# Dart_Controller_SCH2.net
KiCad netlist of a schematic drawn in Altium Designer
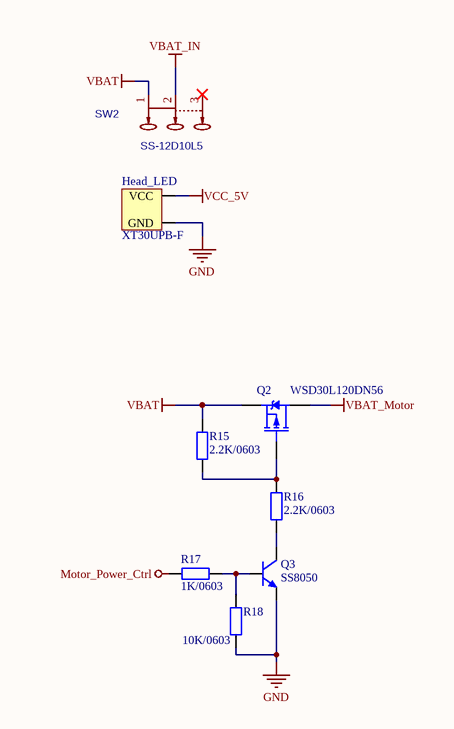
[diagram p0: Dart_Controller_SCH2.SchDoc]

(export (version "E")
  (design (tool "Eeschema 10.0.6"))
  (components
    (comp (ref "Head_LED")
      (value "XT30UPB-F")
      (footprint "XT30PW-F")
      (description "母头（卧式）")
      (libsource (lib "Dart_Controller_Schlib") (part "XT30-PW-F"))
    )
    (comp (ref "Q2")
      (value "WSD30L120DN56")
      (footprint "POWERVDFN-8_L6.0-W5.0-P1.27-BL")
      (description "P沟道场效应管")
      (libsource (lib "Dart_Controller_Schlib") (part "WSD30L120DN56"))
    )
    (comp (ref "Q3")
      (value "SS8050")
      (footprint "SOT23-3L")
      (description "高频放大-NPN型")
      (fields (field (name "版权归属") "封装库来自淘宝 ID：黄晶宝石"))
      (libsource (lib "Dart_Controller_Schlib") (part "SS8050-SMD"))
    )
    (comp (ref "R15")
      (value "2.2K/0603")
      (footprint "R 0603_M")
      (description "贴片电阻")
      (fields (field (name "版权归属") "来自淘宝 ID：黄晶宝石"))
      (libsource (lib "Dart_Controller_Schlib") (part "R 0603"))
    )
    (comp (ref "R16")
      (value "2.2K/0603")
      (footprint "R 0603_M")
      (description "贴片电阻")
      (fields (field (name "版权归属") "来自淘宝 ID：黄晶宝石"))
      (libsource (lib "Dart_Controller_Schlib") (part "R 0603"))
    )
    (comp (ref "R17")
      (value "1K/0603")
      (footprint "R 0603_M")
      (description "贴片电阻")
      (fields (field (name "版权归属") "来自淘宝 ID：黄晶宝石"))
      (libsource (lib "Dart_Controller_Schlib") (part "R 0603"))
    )
    (comp (ref "R18")
      (value "10K/0603")
      (footprint "R 0603_M")
      (description "贴片电阻")
      (fields (field (name "版权归属") "来自淘宝 ID：黄晶宝石"))
      (libsource (lib "Dart_Controller_Schlib") (part "R 0603"))
    )
    (comp (ref "SW2")
      (value "SS-12D10L5")
      (footprint "SW-TH_SS-12D10L5")
      (description "滑动开关")
      (fields (field (name "MANUFACTURER") "XKB Connectivity(中国星坤)") (field (name "CONTRIBUTOR") "LCSC"))
      (libsource (lib "Dart_Controller_Schlib") (part "SS-12D10L5"))
    )
  )
  (nets
    (net (code "1") (name "GND") (class "Default")
      (node (ref "Head_LED") (pin "2") (pinfunction "GND_2") (pintype "passive"))
      (node (ref "Q3") (pin "2") (pinfunction "E_2") (pintype "passive"))
      (node (ref "R18") (pin "2") (pinfunction "2_2") (pintype "passive"))
    )
    (net (code "2") (name "Motor_Power_Ctrl") (class "Default")
      (node (ref "R17") (pin "2") (pinfunction "2_2") (pintype "passive"))
    )
    (net (code "3") (name "Net-(Q2-PadG)") (class "Default")
      (node (ref "Q2") (pin "G") (pinfunction "G_G") (pintype "passive"))
      (node (ref "R15") (pin "1") (pinfunction "1_1") (pintype "passive"))
      (node (ref "R16") (pin "2") (pinfunction "2_2") (pintype "passive"))
    )
    (net (code "4") (name "Net-(Q3-B)") (class "Default")
      (node (ref "Q3") (pin "1") (pinfunction "B_1") (pintype "passive"))
      (node (ref "R17") (pin "1") (pinfunction "1_1") (pintype "passive"))
      (node (ref "R18") (pin "1") (pinfunction "1_1") (pintype "passive"))
    )
    (net (code "5") (name "Net-(Q3-C)") (class "Default")
      (node (ref "Q3") (pin "3") (pinfunction "C_3") (pintype "passive"))
      (node (ref "R16") (pin "1") (pinfunction "1_1") (pintype "passive"))
    )
    (net (code "6") (name "VBAT") (class "Default")
      (node (ref "Q2") (pin "S") (pinfunction "S_S") (pintype "passive"))
      (node (ref "R15") (pin "2") (pinfunction "2_2") (pintype "passive"))
      (node (ref "SW2") (pin "1") (pinfunction "1_1") (pintype "passive"))
    )
    (net (code "7") (name "VBAT_IN") (class "Default")
      (node (ref "SW2") (pin "2") (pinfunction "2_2") (pintype "passive"))
    )
    (net (code "8") (name "VBAT_Motor") (class "Default")
      (node (ref "Q2") (pin "D") (pinfunction "D_D") (pintype "passive"))
    )
    (net (code "9") (name "VCC_5V") (class "Default")
      (node (ref "Head_LED") (pin "1") (pinfunction "VCC_1") (pintype "passive"))
    )
    (net (code "10") (name "unconnected-(SW2-Pad3)") (class "Default")
      (node (ref "SW2") (pin "3") (pinfunction "3_3") (pintype "passive+no_connect"))
    )
  )
)
